# PFD_Board.net
KiCad netlist of a schematic drawn in EAGLE
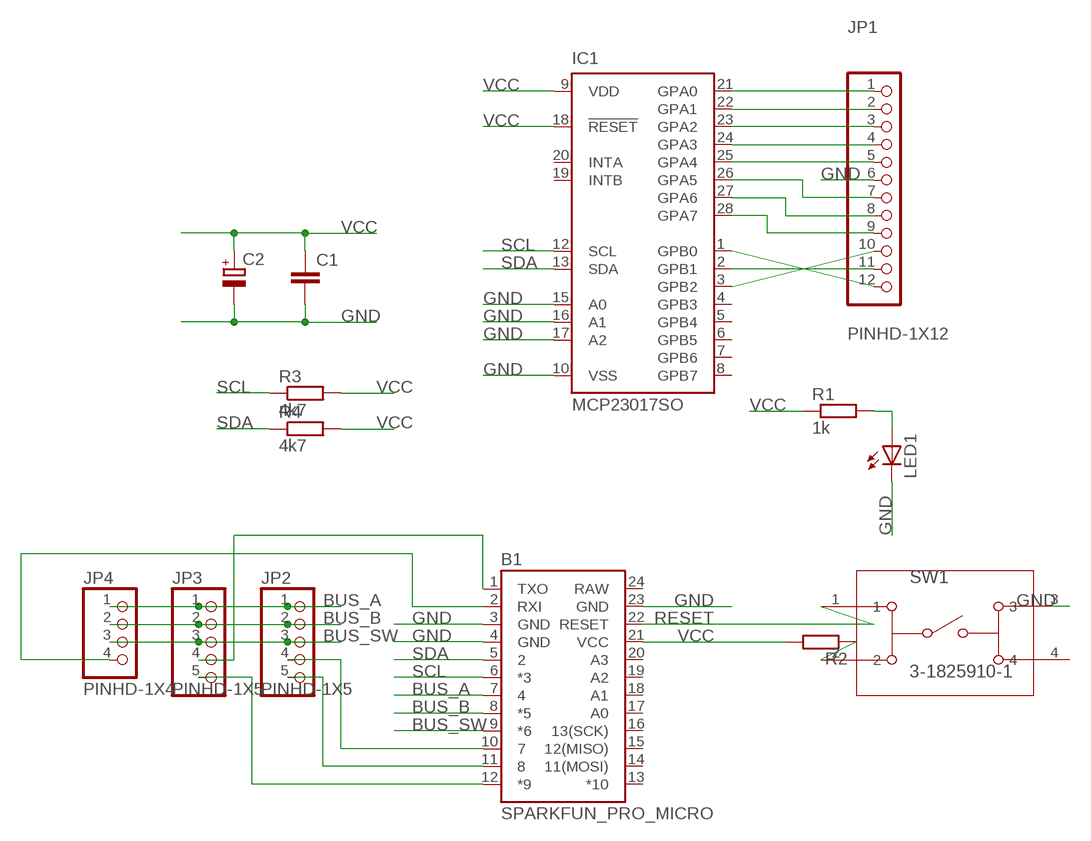
[diagram p0: schematic, sheet 1]

(export (version "E")
  (design (tool "Eeschema 10.0.6"))
  (components
    (comp (ref "B1")
      (value "SPARKFUN_PRO_MICRO")
      (footprint "eagle-import:SPARKFUN_PRO_MICRO")
      (libsource (lib "eagle-import") (part "SPARKFUN_PRO_MICRO"))
    )
    (comp (ref "C1")
      (value "C-EU025-025X050")
      (footprint "eagle-import:C025-025X050")
      (libsource (lib "eagle-import") (part "C-EU025-025X050"))
    )
    (comp (ref "C2")
      (value "CPOL-EUE2.5-5")
      (footprint "eagle-import:E2,5-5")
      (libsource (lib "eagle-import") (part "CPOL-EUE2.5-5"))
    )
    (comp (ref "IC1")
      (value "MCP23017SO")
      (footprint "eagle-import:SO28W")
      (libsource (lib "eagle-import") (part "MCP23017SO"))
    )
    (comp (ref "JP1")
      (value "PINHD-1X12")
      (footprint "eagle-import:1X12")
      (libsource (lib "eagle-import") (part "PINHD-1X12"))
    )
    (comp (ref "JP2")
      (value "PINHD-1X5")
      (footprint "eagle-import:1X05")
      (libsource (lib "eagle-import") (part "PINHD-1X5"))
    )
    (comp (ref "JP3")
      (value "PINHD-1X5")
      (footprint "eagle-import:1X05")
      (libsource (lib "eagle-import") (part "PINHD-1X5"))
    )
    (comp (ref "JP4")
      (value "PINHD-1X4")
      (footprint "eagle-import:1X04")
      (libsource (lib "eagle-import") (part "PINHD-1X4"))
    )
    (comp (ref "LED1")
      (value "LED3MM")
      (footprint "eagle-import:LED3MM")
      (libsource (lib "eagle-import") (part "LED3MM"))
    )
    (comp (ref "R1")
      (value "1k")
      (footprint "eagle-import:0207_10")
      (libsource (lib "eagle-import") (part "R-EU_0207/10"))
    )
    (comp (ref "R2")
      (value "R-EU_0207/10")
      (footprint "eagle-import:0207_10")
      (libsource (lib "eagle-import") (part "R-EU_0207/10"))
    )
    (comp (ref "R3")
      (value "4k7")
      (footprint "eagle-import:0207_10")
      (libsource (lib "eagle-import") (part "R-EU_0207/10"))
    )
    (comp (ref "R4")
      (value "4k7")
      (footprint "eagle-import:0207_10")
      (libsource (lib "eagle-import") (part "R-EU_0207/10"))
    )
    (comp (ref "SW1")
      (value "3-1825910-1")
      (footprint "eagle-import:SW4_1825910-H")
      (fields (field (name "COPYRIGHT") "Copyright (C) 2016 Accelerated Designs. All rights reserved"))
      (libsource (lib "eagle-import") (part "3-1825910-1"))
    )
  )
  (nets
    (net (code "1") (name "/BUS_A") (class "Default")
      (node (ref "B1") (pin "7") (pinfunction "4_7") (pintype "bidirectional"))
      (node (ref "JP2") (pin "1") (pinfunction "1_1") (pintype "passive"))
      (node (ref "JP3") (pin "1") (pinfunction "1_1") (pintype "passive"))
      (node (ref "JP4") (pin "1") (pinfunction "1_1") (pintype "passive"))
    )
    (net (code "2") (name "/BUS_B") (class "Default")
      (node (ref "B1") (pin "8") (pinfunction "*5_8") (pintype "bidirectional"))
      (node (ref "JP2") (pin "2") (pinfunction "2_2") (pintype "passive"))
      (node (ref "JP3") (pin "2") (pinfunction "2_2") (pintype "passive"))
      (node (ref "JP4") (pin "2") (pinfunction "2_2") (pintype "passive"))
    )
    (net (code "3") (name "/BUS_SW") (class "Default")
      (node (ref "B1") (pin "9") (pinfunction "*6_9") (pintype "bidirectional"))
      (node (ref "JP2") (pin "3") (pinfunction "3_3") (pintype "passive"))
      (node (ref "JP3") (pin "3") (pinfunction "3_3") (pintype "passive"))
      (node (ref "JP4") (pin "3") (pinfunction "3_3") (pintype "passive"))
    )
    (net (code "4") (name "/GND") (class "Default")
      (node (ref "B1") (pin "23") (pinfunction "GND_23") (pintype "power_in"))
      (node (ref "B1") (pin "3") (pinfunction "GND_3") (pintype "power_in"))
      (node (ref "B1") (pin "4") (pinfunction "GND_4") (pintype "power_in"))
      (node (ref "C1") (pin "2") (pinfunction "2_2") (pintype "passive"))
      (node (ref "C2") (pin "-") (pinfunction "-_-") (pintype "passive"))
      (node (ref "IC1") (pin "10") (pinfunction "VSS_10") (pintype "power_in"))
      (node (ref "IC1") (pin "15") (pinfunction "A0_15") (pintype "input"))
      (node (ref "IC1") (pin "16") (pinfunction "A1_16") (pintype "input"))
      (node (ref "IC1") (pin "17") (pinfunction "A2_17") (pintype "input"))
      (node (ref "JP1") (pin "6") (pinfunction "6_6") (pintype "passive"))
      (node (ref "LED1") (pin "K") (pinfunction "C_K") (pintype "passive"))
      (node (ref "SW1") (pin "3") (pinfunction "3_3") (pintype "passive"))
    )
    (net (code "5") (name "/RAW") (class "Default")
      (node (ref "B1") (pin "24") (pinfunction "RAW_24") (pintype "power_in"))
    )
    (net (code "6") (name "/RESET") (class "Default")
      (node (ref "B1") (pin "22") (pinfunction "RESET_22") (pintype "bidirectional"))
      (node (ref "SW1") (pin "1") (pinfunction "1_1") (pintype "passive"))
    )
    (net (code "7") (name "/SCL") (class "Default")
      (node (ref "B1") (pin "6") (pinfunction "*3_6") (pintype "bidirectional"))
      (node (ref "IC1") (pin "12") (pinfunction "SCL_12") (pintype "input"))
      (node (ref "R3") (pin "1") (pinfunction "1_1") (pintype "passive"))
    )
    (net (code "8") (name "/SDA") (class "Default")
      (node (ref "B1") (pin "5") (pinfunction "2_5") (pintype "bidirectional"))
      (node (ref "IC1") (pin "13") (pinfunction "SDA_13") (pintype "bidirectional"))
      (node (ref "R4") (pin "1") (pinfunction "1_1") (pintype "passive"))
    )
    (net (code "9") (name "/VCC") (class "Default")
      (node (ref "B1") (pin "21") (pinfunction "VCC_21") (pintype "power_in"))
      (node (ref "C1") (pin "1") (pinfunction "1_1") (pintype "passive"))
      (node (ref "C2") (pin "+") (pinfunction "+_+") (pintype "passive"))
      (node (ref "IC1") (pin "18") (pinfunction "~{RESET}_18") (pintype "input"))
      (node (ref "IC1") (pin "9") (pinfunction "VDD_9") (pintype "power_in"))
      (node (ref "R1") (pin "1") (pinfunction "1_1") (pintype "passive"))
      (node (ref "R2") (pin "2") (pinfunction "2_2") (pintype "passive"))
      (node (ref "R3") (pin "2") (pinfunction "2_2") (pintype "passive"))
      (node (ref "R4") (pin "2") (pinfunction "2_2") (pintype "passive"))
    )
    (net (code "10") (name "Net-(B1-*9)") (class "Default")
      (node (ref "B1") (pin "12") (pinfunction "*9_12") (pintype "bidirectional"))
      (node (ref "JP3") (pin "5") (pinfunction "5_5") (pintype "passive"))
    )
    (net (code "11") (name "Net-(B1-7)") (class "Default")
      (node (ref "B1") (pin "10") (pinfunction "7_10") (pintype "bidirectional"))
      (node (ref "JP2") (pin "4") (pinfunction "4_4") (pintype "passive"))
    )
    (net (code "12") (name "Net-(B1-8)") (class "Default")
      (node (ref "B1") (pin "11") (pinfunction "8_11") (pintype "bidirectional"))
      (node (ref "JP2") (pin "5") (pinfunction "5_5") (pintype "passive"))
    )
    (net (code "13") (name "Net-(B1-RXI)") (class "Default")
      (node (ref "B1") (pin "2") (pinfunction "RXI_2") (pintype "bidirectional"))
      (node (ref "JP4") (pin "4") (pinfunction "4_4") (pintype "passive"))
    )
    (net (code "14") (name "Net-(B1-TXO)") (class "Default")
      (node (ref "B1") (pin "1") (pinfunction "TXO_1") (pintype "bidirectional"))
      (node (ref "JP3") (pin "4") (pinfunction "4_4") (pintype "passive"))
    )
    (net (code "15") (name "Net-(IC1-GPA0)") (class "Default")
      (node (ref "IC1") (pin "21") (pinfunction "GPA0_21") (pintype "bidirectional"))
      (node (ref "JP1") (pin "1") (pinfunction "1_1") (pintype "passive"))
    )
    (net (code "16") (name "Net-(IC1-GPA1)") (class "Default")
      (node (ref "IC1") (pin "22") (pinfunction "GPA1_22") (pintype "bidirectional"))
      (node (ref "JP1") (pin "2") (pinfunction "2_2") (pintype "passive"))
    )
    (net (code "17") (name "Net-(IC1-GPA2)") (class "Default")
      (node (ref "IC1") (pin "23") (pinfunction "GPA2_23") (pintype "bidirectional"))
      (node (ref "JP1") (pin "3") (pinfunction "3_3") (pintype "passive"))
    )
    (net (code "18") (name "Net-(IC1-GPA3)") (class "Default")
      (node (ref "IC1") (pin "24") (pinfunction "GPA3_24") (pintype "bidirectional"))
      (node (ref "JP1") (pin "4") (pinfunction "4_4") (pintype "passive"))
    )
    (net (code "19") (name "Net-(IC1-GPA4)") (class "Default")
      (node (ref "IC1") (pin "25") (pinfunction "GPA4_25") (pintype "bidirectional"))
      (node (ref "JP1") (pin "5") (pinfunction "5_5") (pintype "passive"))
    )
    (net (code "20") (name "Net-(IC1-GPA5)") (class "Default")
      (node (ref "IC1") (pin "26") (pinfunction "GPA5_26") (pintype "bidirectional"))
      (node (ref "JP1") (pin "7") (pinfunction "7_7") (pintype "passive"))
    )
    (net (code "21") (name "Net-(IC1-GPA6)") (class "Default")
      (node (ref "IC1") (pin "27") (pinfunction "GPA6_27") (pintype "bidirectional"))
      (node (ref "JP1") (pin "8") (pinfunction "8_8") (pintype "passive"))
    )
    (net (code "22") (name "Net-(IC1-GPA7)") (class "Default")
      (node (ref "IC1") (pin "28") (pinfunction "GPA7_28") (pintype "bidirectional"))
      (node (ref "JP1") (pin "9") (pinfunction "9_9") (pintype "passive"))
    )
    (net (code "23") (name "Net-(IC1-GPB0)") (class "Default")
      (node (ref "IC1") (pin "1") (pinfunction "GPB0_1") (pintype "bidirectional"))
      (node (ref "JP1") (pin "12") (pinfunction "12_12") (pintype "passive"))
    )
    (net (code "24") (name "Net-(IC1-GPB1)") (class "Default")
      (node (ref "IC1") (pin "2") (pinfunction "GPB1_2") (pintype "bidirectional"))
      (node (ref "JP1") (pin "11") (pinfunction "11_11") (pintype "passive"))
    )
    (net (code "25") (name "Net-(IC1-GPB2)") (class "Default")
      (node (ref "IC1") (pin "3") (pinfunction "GPB2_3") (pintype "bidirectional"))
      (node (ref "JP1") (pin "10") (pinfunction "10_10") (pintype "passive"))
    )
    (net (code "26") (name "Net-(LED1-PadA)") (class "Default")
      (node (ref "LED1") (pin "A") (pinfunction "A_A") (pintype "passive"))
      (node (ref "R1") (pin "2") (pinfunction "2_2") (pintype "passive"))
    )
    (net (code "27") (name "Net-(R2-Pad1)") (class "Default")
      (node (ref "R2") (pin "1") (pinfunction "1_1") (pintype "passive"))
      (node (ref "SW1") (pin "2") (pinfunction "2_2") (pintype "passive"))
    )
    (net (code "28") (name "unconnected-(B1-*10-Pad13)") (class "Default")
      (node (ref "B1") (pin "13") (pinfunction "*10_13") (pintype "bidirectional"))
    )
    (net (code "29") (name "unconnected-(B1-11(MOSI)-Pad14)") (class "Default")
      (node (ref "B1") (pin "14") (pinfunction "11(MOSI)_14") (pintype "bidirectional"))
    )
    (net (code "30") (name "unconnected-(B1-12(MISO)-Pad15)") (class "Default")
      (node (ref "B1") (pin "15") (pinfunction "12(MISO)_15") (pintype "bidirectional"))
    )
    (net (code "31") (name "unconnected-(B1-13(SCK)-Pad16)") (class "Default")
      (node (ref "B1") (pin "16") (pinfunction "13(SCK)_16") (pintype "bidirectional"))
    )
    (net (code "32") (name "unconnected-(B1-A0-Pad17)") (class "Default")
      (node (ref "B1") (pin "17") (pinfunction "A0_17") (pintype "bidirectional"))
    )
    (net (code "33") (name "unconnected-(B1-A1-Pad18)") (class "Default")
      (node (ref "B1") (pin "18") (pinfunction "A1_18") (pintype "bidirectional"))
    )
    (net (code "34") (name "unconnected-(B1-A2-Pad19)") (class "Default")
      (node (ref "B1") (pin "19") (pinfunction "A2_19") (pintype "bidirectional"))
    )
    (net (code "35") (name "unconnected-(B1-A3-Pad20)") (class "Default")
      (node (ref "B1") (pin "20") (pinfunction "A3_20") (pintype "bidirectional"))
    )
    (net (code "36") (name "unconnected-(IC1-GPB3-Pad4)") (class "Default")
      (node (ref "IC1") (pin "4") (pinfunction "GPB3_4") (pintype "bidirectional"))
    )
    (net (code "37") (name "unconnected-(IC1-GPB4-Pad5)") (class "Default")
      (node (ref "IC1") (pin "5") (pinfunction "GPB4_5") (pintype "bidirectional"))
    )
    (net (code "38") (name "unconnected-(IC1-GPB5-Pad6)") (class "Default")
      (node (ref "IC1") (pin "6") (pinfunction "GPB5_6") (pintype "bidirectional"))
    )
    (net (code "39") (name "unconnected-(IC1-GPB6-Pad7)") (class "Default")
      (node (ref "IC1") (pin "7") (pinfunction "GPB6_7") (pintype "bidirectional"))
    )
    (net (code "40") (name "unconnected-(IC1-GPB7-Pad8)") (class "Default")
      (node (ref "IC1") (pin "8") (pinfunction "GPB7_8") (pintype "bidirectional"))
    )
    (net (code "41") (name "unconnected-(IC1-INTA-Pad20)") (class "Default")
      (node (ref "IC1") (pin "20") (pinfunction "INTA_20") (pintype "output"))
    )
    (net (code "42") (name "unconnected-(IC1-INTB-Pad19)") (class "Default")
      (node (ref "IC1") (pin "19") (pinfunction "INTB_19") (pintype "output"))
    )
    (net (code "43") (name "unconnected-(SW1-Pad4)") (class "Default")
      (node (ref "SW1") (pin "4") (pinfunction "4_4") (pintype "passive"))
    )
  )
)
